# Power.net
KiCad netlist of a schematic drawn in Altium Designer
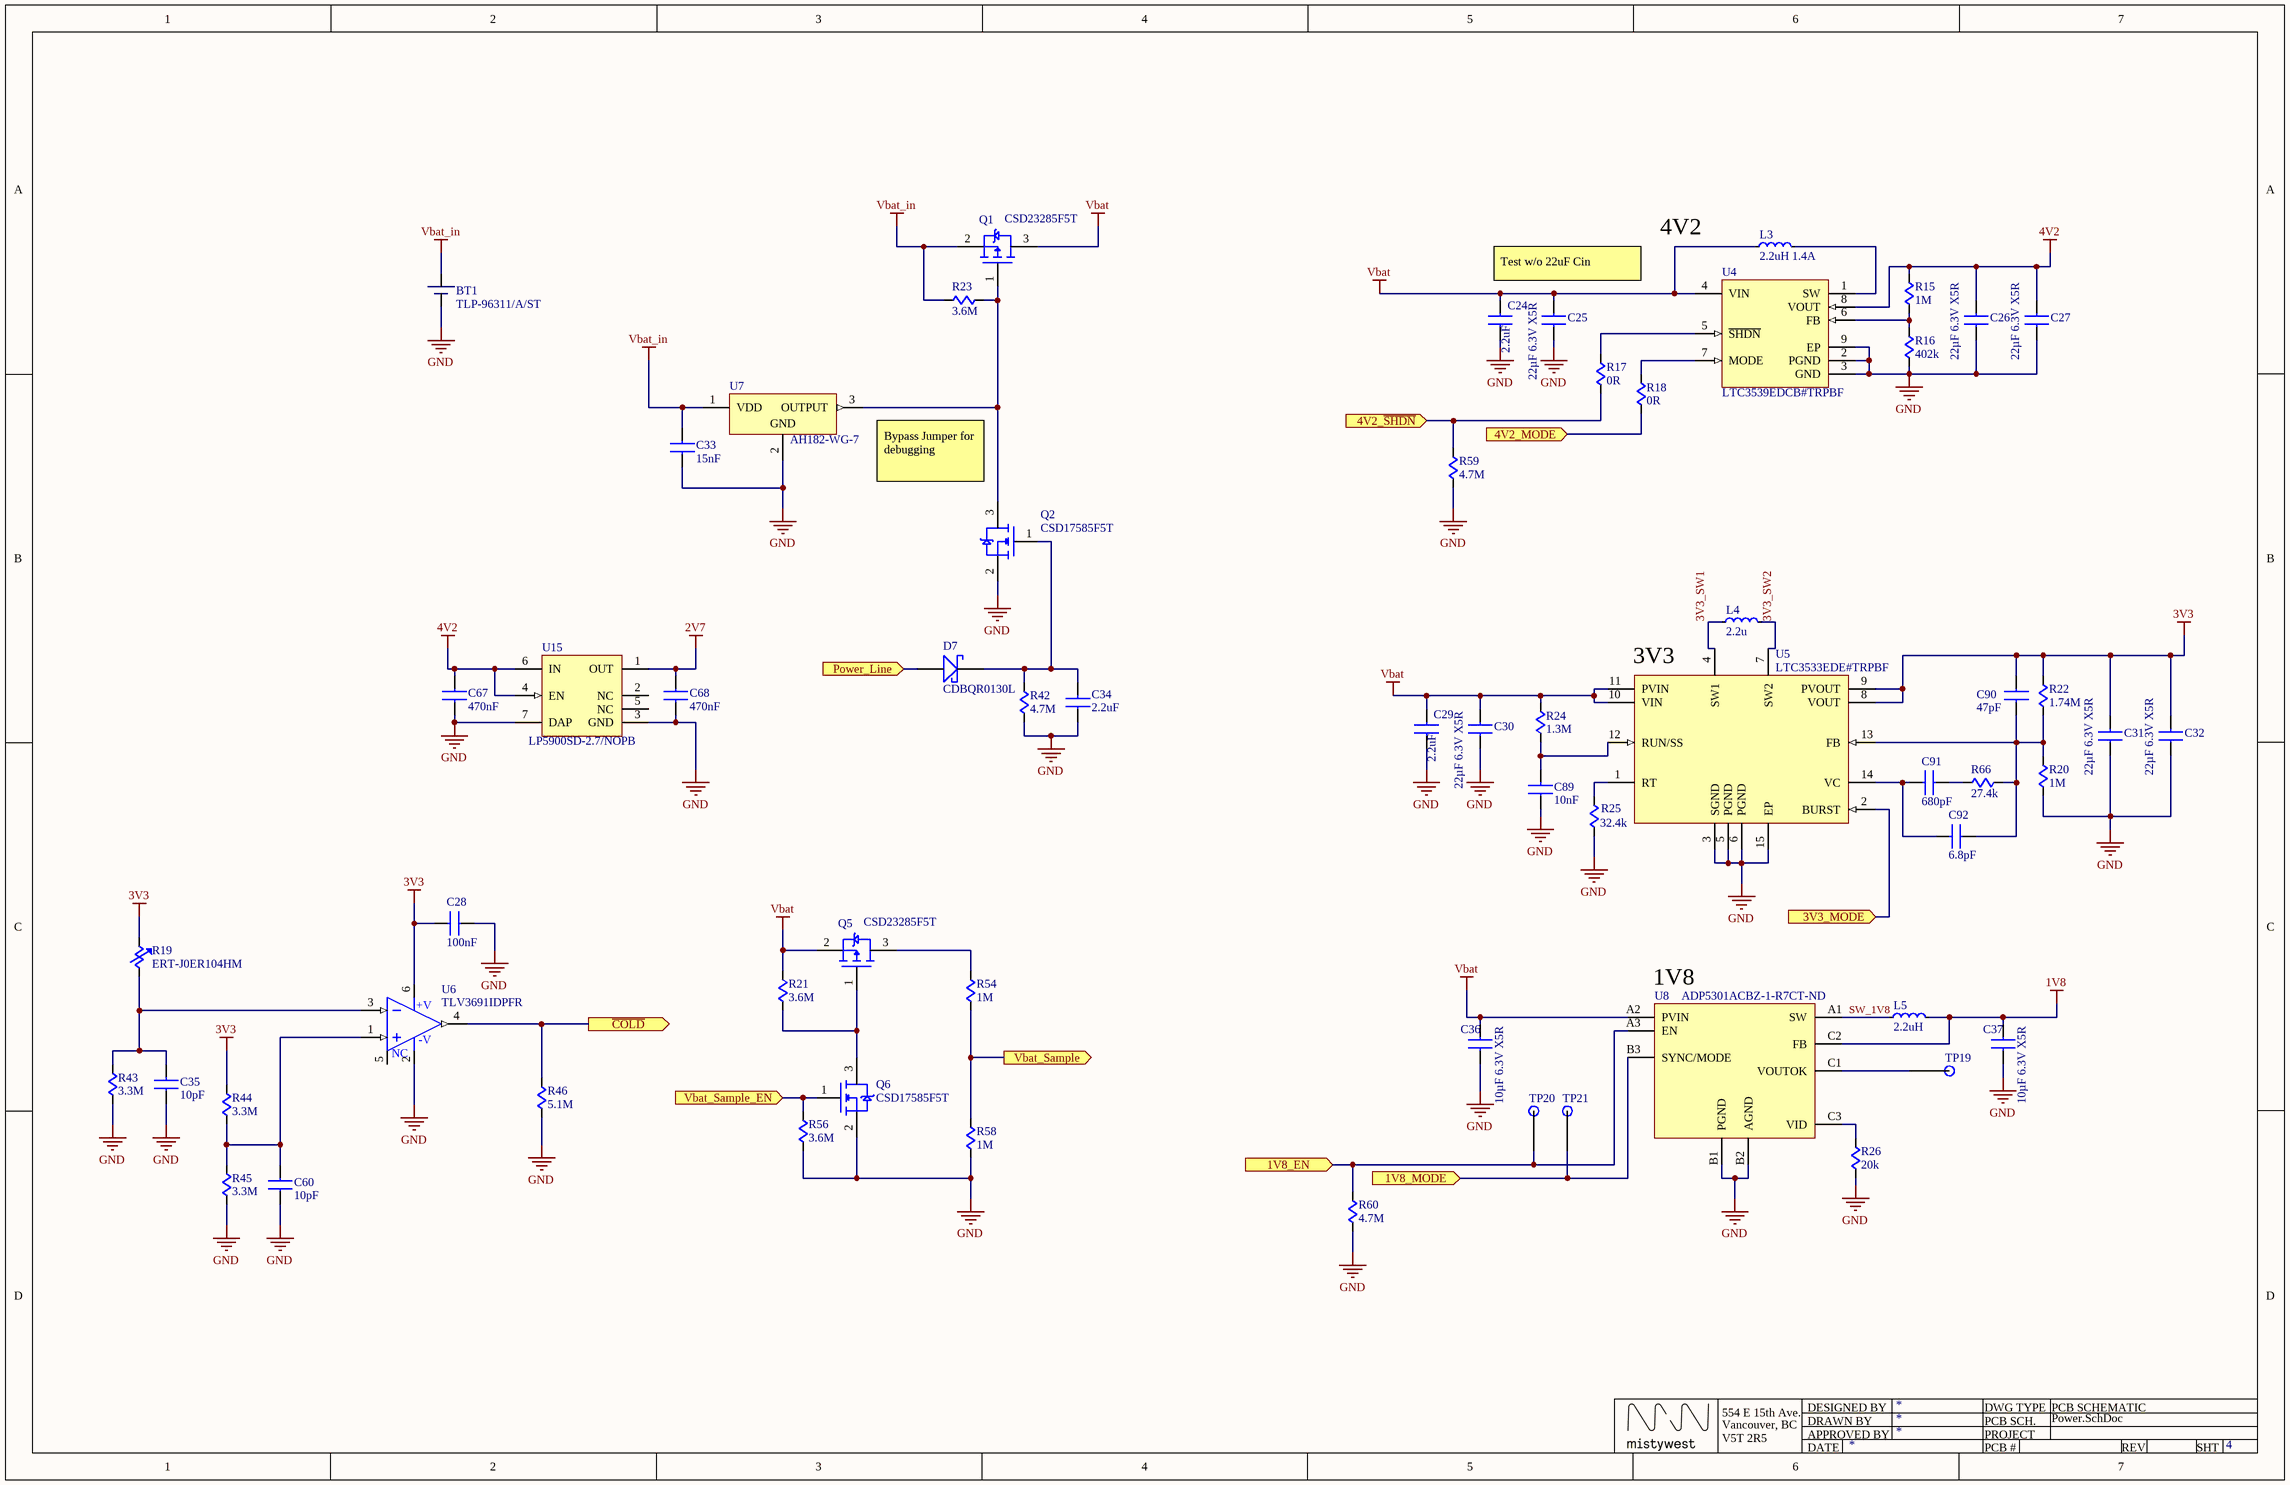
[diagram p0: Power.SchDoc]

(export (version "E")
  (design (tool "Eeschema 10.0.6"))
  (components
    (comp (ref "BT1")
      (value "TLP-96311/A/ST")
      (footprint "TLP-96311/A/ST")
      (fields (field (name "MANUFACTURER") "Tadiran"))
      (libsource (lib "Misty West") (part "1C"))
    )
    (comp (ref "C24")
      (value "2.2uF")
      (footprint "CAPC1608N-0603")
      (description "CAP CER 2.2uF 6.3V X7R 0603 ±10%")
      (fields
        (field (name "MANUFACTURER") "Samsung Electro-Mechanics America, Inc.")
        (field (name "MANUFACTURER PART NUMBER") "CL10B225KQ8NNNC")
      )
      (libsource (lib "") (part "Component_1_1"))
    )
    (comp (ref "C25")
      (value "22µF 6.3V X5R")
      (footprint "CAPC1608N-0603")
      (description "CAP CER 22UF 6.3V X5R 0603 ±10%")
      (fields
        (field (name "MANUFACTURER") "Samsung Electro-Mechanics America, Inc.")
        (field (name "MANUFACTURER PART NUMBER") "CL10A226KQ8NRNE")
      )
      (libsource (lib "") (part "Component_1_1"))
    )
    (comp (ref "C26")
      (value "22µF 6.3V X5R")
      (footprint "CAPC1608N-0603")
      (description "CAP CER 22UF 6.3V X5R 0603 ±10%")
      (fields
        (field (name "MANUFACTURER") "Samsung Electro-Mechanics America, Inc.")
        (field (name "MANUFACTURER PART NUMBER") "CL10A226KQ8NRNE")
      )
      (libsource (lib "") (part "Component_1_1"))
    )
    (comp (ref "C27")
      (value "22µF 6.3V X5R")
      (footprint "CAPC1608N-0603")
      (description "CAP CER 22UF 6.3V X5R 0603 ±10%")
      (fields
        (field (name "MANUFACTURER") "Samsung Electro-Mechanics America, Inc.")
        (field (name "MANUFACTURER PART NUMBER") "CL10A226KQ8NRNE")
      )
      (libsource (lib "") (part "Component_1_1"))
    )
    (comp (ref "C28")
      (value "100nF")
      (footprint "CAPC1005N-0402")
      (description "CAP CER 0.1UF 10V X7R 0402 ±5%")
      (fields
        (field (name "MANUFACTURER") "Samsung Electro-Mechanics America, Inc.")
        (field (name "MANUFACTURER PART NUMBER") "CL05B104JP5NNNC")
      )
      (libsource (lib "") (part "Component_1_1"))
    )
    (comp (ref "C29")
      (value "2.2uF")
      (footprint "CAPC1608N-0603")
      (description "CAP CER 2.2uF 6.3V X7R 0603 ±10%")
      (fields
        (field (name "MANUFACTURER") "Samsung Electro-Mechanics America, Inc.")
        (field (name "MANUFACTURER PART NUMBER") "CL10B225KQ8NNNC")
      )
      (libsource (lib "") (part "Component_1_1"))
    )
    (comp (ref "C30")
      (value "22µF 6.3V X5R")
      (footprint "CAPC1608N-0603")
      (description "CAP CER 22UF 6.3V X5R 0603 ±10%")
      (fields
        (field (name "MANUFACTURER") "Samsung Electro-Mechanics America, Inc.")
        (field (name "MANUFACTURER PART NUMBER") "CL10A226KQ8NRNE")
      )
      (libsource (lib "") (part "Component_1_1"))
    )
    (comp (ref "C31")
      (value "22µF 6.3V X5R")
      (footprint "CAPC1608N-0603")
      (description "CAP CER 22UF 6.3V X5R 0603 ±10%")
      (fields
        (field (name "MANUFACTURER") "Samsung Electro-Mechanics America, Inc.")
        (field (name "MANUFACTURER PART NUMBER") "CL10A226KQ8NRNE")
      )
      (libsource (lib "") (part "Component_1_1"))
    )
    (comp (ref "C32")
      (value "22µF 6.3V X5R")
      (footprint "CAPC1608N-0603")
      (description "CAP CER 22UF 6.3V X5R 0603 ±10%")
      (fields
        (field (name "MANUFACTURER") "Samsung Electro-Mechanics America, Inc.")
        (field (name "MANUFACTURER PART NUMBER") "CL10A226KQ8NRNE")
      )
      (libsource (lib "") (part "Component_1_1"))
    )
    (comp (ref "C33")
      (value "15nF")
      (footprint "CAPC60X30X33L15N")
      (description "CAP CER 15nF 6.3V X5R 0201 ±10%")
      (fields
        (field (name "MANUFACTURER") "Samsung Electro-Mechanics America, Inc.")
        (field (name "MANUFACTURER PART NUMBER") "CL03A153KQ3NNNC")
      )
      (libsource (lib "") (part "Component_1_1"))
    )
    (comp (ref "C34")
      (value "2.2uF")
      (footprint "CAPC1608N-0603")
      (description "CAP CER 2.2uF 6.3V X7R 0603 ±10%")
      (fields
        (field (name "MANUFACTURER") "Samsung Electro-Mechanics America, Inc.")
        (field (name "MANUFACTURER PART NUMBER") "CL10B225KQ8NNNC")
      )
      (libsource (lib "") (part "Component_1_1"))
    )
    (comp (ref "C35")
      (value "10pF")
      (footprint "CAPC1005N-0402")
      (description "CAP CER 10PF 50V C0G/NP0 0402 ±0.5pF")
      (fields
        (field (name "MANUFACTURER") "Samsung Electro-Mechanics America, Inc.")
        (field (name "MANUFACTURER PART NUMBER") "CL05C100DB5NNNC")
      )
      (libsource (lib "") (part "Component_1_1"))
    )
    (comp (ref "C36")
      (value "10µF 6.3V X5R")
      (footprint "CAPC1608N-0603")
      (description "CAP CER 10UF 6.3V X5R 0603 ±10%")
      (fields
        (field (name "MANUFACTURER") "Samsung Electro-Mechanics America, Inc.")
        (field (name "MANUFACTURER PART NUMBER") "CL10A106KQ8NNNC")
      )
      (libsource (lib "") (part "Component_1_1"))
    )
    (comp (ref "C37")
      (value "10µF 6.3V X5R")
      (footprint "CAPC1608N-0603")
      (description "CAP CER 10UF 6.3V X5R 0603 ±10%")
      (fields
        (field (name "MANUFACTURER") "Samsung Electro-Mechanics America, Inc.")
        (field (name "MANUFACTURER PART NUMBER") "CL10A106KQ8NNNC")
      )
      (libsource (lib "") (part "Component_1_1"))
    )
    (comp (ref "C60")
      (value "10pF")
      (footprint "CAPC1005N-0402")
      (description "CAP CER 10PF 50V C0G/NP0 0402 ±0.5pF")
      (fields
        (field (name "MANUFACTURER") "Samsung Electro-Mechanics America, Inc.")
        (field (name "MANUFACTURER PART NUMBER") "CL05C100DB5NNNC")
      )
      (libsource (lib "") (part "Component_1_1"))
    )
    (comp (ref "C67")
      (value "470nF")
      (footprint "CAPC60X30X33L15N")
      (description "CAP CER 470nF 6.3V X5R 0201 ±10%")
      (fields
        (field (name "MANUFACTURER") "Samsung Electro-Mechanics America, Inc.")
        (field (name "MANUFACTURER PART NUMBER") "CL03A474KQ3NNNC")
      )
      (libsource (lib "") (part "Component_1_1"))
    )
    (comp (ref "C68")
      (value "470nF")
      (footprint "CAPC60X30X33L15N")
      (description "CAP CER 470nF 6.3V X5R 0201 ±10%")
      (fields
        (field (name "MANUFACTURER") "Samsung Electro-Mechanics America, Inc.")
        (field (name "MANUFACTURER PART NUMBER") "CL03A474KQ3NNNC")
      )
      (libsource (lib "") (part "Component_1_1"))
    )
    (comp (ref "C89")
      (value "10nF")
      (footprint "CAPC1005N-0402")
      (description "CAP CER 10000PF 10V X7R 0402 ±10%")
      (fields
        (field (name "MANUFACTURER") "Samsung Electro-Mechanics America, Inc.")
        (field (name "MANUFACTURER PART NUMBER") "CL05B103KP5NNNC")
      )
      (libsource (lib "") (part "Component_1_1"))
    )
    (comp (ref "C90")
      (value "47pF")
      (footprint "CAPC1005N-0402")
      (description "CAP CER 47PF 50V C0G/NP0 0402 ±5% AEC-Q200")
      (fields
        (field (name "MANUFACTURER") "Samsung Electro-Mechanics America, Inc.")
        (field (name "MANUFACTURER PART NUMBER") "CL05C470JB51PNC")
      )
      (libsource (lib "") (part "Component_1_1"))
    )
    (comp (ref "C91")
      (value "680pF")
      (footprint "CAPC1005N-0402")
      (description "CAP CER 680PF 50V C0G/NP0 0402 ±5%")
      (fields
        (field (name "MANUFACTURER") "Samsung Electro-Mechanics America, Inc.")
        (field (name "MANUFACTURER PART NUMBER") "CL05C681JB5NNNC")
      )
      (libsource (lib "") (part "Component_1_1"))
    )
    (comp (ref "C92")
      (value "6.8pF")
      (footprint "CAPC1005N-0402")
      (description "CAP CER 6.8PF 50V C0G/NP0 0402 ±0.25pF")
      (fields
        (field (name "MANUFACTURER") "Samsung Electro-Mechanics America, Inc.")
        (field (name "MANUFACTURER PART NUMBER") "CL05C6R8CB5NNNC")
      )
      (libsource (lib "") (part "Component_1_1"))
    )
    (comp (ref "D7")
      (value "CDBQR0130L")
      (footprint "CDBQR0130L")
      (description "Diode Schottky 30V 100mA Surface Mount 0402/SOD-923F")
      (fields (field (name "MANUFACTURER") "Comchip Technology"))
      (libsource (lib "") (part "Component_1_2"))
    )
    (comp (ref "L3")
      (value "2.2uH 1.4A")
      (footprint "XFL3012")
      (description "XFL3012-222ME_")
      (fields (field (name "MANUFACTURER") "CoilCraft"))
      (libsource (lib "") (part "Component_1_4"))
    )
    (comp (ref "L4")
      (value "2.2u")
      (footprint "XAL4020")
      (description "XAL4020-222ME")
      (fields (field (name "MANUFACTURER") "CoilCraft"))
      (libsource (lib "") (part "Component_1_4"))
    )
    (comp (ref "L5")
      (value "2.2uH")
      (footprint "XPL2010")
      (description "XPL2010-222ML")
      (fields (field (name "MANUFACTURER") "CoilCraft"))
      (libsource (lib "") (part "Component_1_4"))
    )
    (comp (ref "Q1")
      (value "CSD23285F5T")
      (footprint "3-XFDFN")
      (description "P-Channel 12V 5.4A (Ta) 500mW (Ta) Surface Mount 3-PICOSTAR")
      (fields (field (name "MANUFACTURER") "Texas Instruments"))
      (libsource (lib "Misty West") (part "Mosfet-P-CH, 8Pin"))
    )
    (comp (ref "Q2")
      (value "CSD17585F5T")
      (footprint "3-XFDFN")
      (description "N-Channel 30V 5.9A (Ta) 500mW (Ta) Surface Mount 3-PICOSTAR")
      (fields (field (name "MANUFACTURER") "Texas Instruments"))
      (libsource (lib "") (part "Component_1_3"))
    )
    (comp (ref "Q5")
      (value "CSD23285F5T")
      (footprint "3-XFDFN")
      (description "P-Channel 12V 5.4A (Ta) 500mW (Ta) Surface Mount 3-PICOSTAR")
      (fields (field (name "MANUFACTURER") "Texas Instruments"))
      (libsource (lib "Misty West") (part "Mosfet-P-CH, 8Pin"))
    )
    (comp (ref "Q6")
      (value "CSD17585F5T")
      (footprint "3-XFDFN")
      (description "N-Channel 30V 5.9A (Ta) 500mW (Ta) Surface Mount 3-PICOSTAR")
      (fields (field (name "MANUFACTURER") "Texas Instruments"))
      (libsource (lib "") (part "Component_1_3"))
    )
    (comp (ref "R15")
      (value "1M")
      (footprint "RESC0402(1005)_N")
      (description "RES SMD 1M OHM 1% 1/16W 0402")
      (fields
        (field (name "MANUFACTURER") "Yageo")
        (field (name "MANUFACTURER PART NUMBER") "RC0402FR-071ML")
      )
      (libsource (lib "Misty West") (part "Component_1"))
    )
    (comp (ref "R16")
      (value "402k")
      (footprint "RESC0402(1005)_N")
      (description "RES SMD 402K OHM 1% 1/10W 0402")
      (fields
        (field (name "MANUFACTURER") "Panasonic Electronic Components")
        (field (name "MANUFACTURER PART NUMBER") "ERJ-2RKF4023X")
      )
      (libsource (lib "Misty West") (part "Component_1"))
    )
    (comp (ref "R17")
      (value "0R")
      (footprint "Chip Res 1608_0603 MMC")
      (description "0R 0.1W")
      (fields
        (field (name "MANUFACTURER") "Yageo")
        (field (name "MANUFACTURER PART NUMBER") "RC0603JR-070RL")
      )
      (libsource (lib "Misty West") (part "Component_1"))
    )
    (comp (ref "R18")
      (value "0R")
      (footprint "Chip Res 1608_0603 MMC")
      (description "0R 0.1W")
      (fields
        (field (name "MANUFACTURER") "Yageo")
        (field (name "MANUFACTURER PART NUMBER") "RC0603JR-070RL")
      )
      (libsource (lib "Misty West") (part "Component_1"))
    )
    (comp (ref "R19")
      (value "ERT-J0ER104HM")
      (footprint "RESC0402(1005)_N")
      (description "NTC Thermistor 100k 0402 (1005 Metric)")
      (fields (field (name "MANUFACTURER") "Panasonic Electronic Components") (field (name "POWER") "66mW"))
      (libsource (lib "") (part "Component_1_5"))
    )
    (comp (ref "R20")
      (value "1M")
      (footprint "RESC0402(1005)_N")
      (description "RES SMD 1M OHM 1% 1/16W 0402")
      (fields
        (field (name "MANUFACTURER") "Yageo")
        (field (name "MANUFACTURER PART NUMBER") "RC0402FR-071ML")
      )
      (libsource (lib "Misty West") (part "Component_1"))
    )
    (comp (ref "R21")
      (value "3.6M")
      (footprint "RESC0402(1005)_N")
      (description "RES SMD 3.6M OHM 1% 1/16W 0402")
      (fields
        (field (name "MANUFACTURER") "Yageo")
        (field (name "MANUFACTURER PART NUMBER") "RC0402FR-073M6L")
      )
      (libsource (lib "Misty West") (part "Component_1"))
    )
    (comp (ref "R22")
      (value "1.74M")
      (footprint "RESC0402(1005)_N")
      (description "RES SMD 1.74M OHM 1% 1/16W 0402")
      (fields
        (field (name "MANUFACTURER") "Yageo")
        (field (name "MANUFACTURER PART NUMBER") "RC0402FR-071M74L")
      )
      (libsource (lib "Misty West") (part "Component_1"))
    )
    (comp (ref "R23")
      (value "3.6M")
      (footprint "RESC0402(1005)_N")
      (description "RES SMD 3.6M OHM 1% 1/16W 0402")
      (fields
        (field (name "MANUFACTURER") "Yageo")
        (field (name "MANUFACTURER PART NUMBER") "RC0402FR-073M6L")
      )
      (libsource (lib "Misty West") (part "Component_1"))
    )
    (comp (ref "R24")
      (value "1.3M")
      (footprint "RESC0402(1005)_N")
      (description "RES SMD 1.3M OHM 1% 1/16W 0402")
      (fields
        (field (name "MANUFACTURER") "Yageo")
        (field (name "MANUFACTURER PART NUMBER") "RC0402FR-071M3L")
      )
      (libsource (lib "Misty West") (part "Component_1"))
    )
    (comp (ref "R25")
      (value "32.4k")
      (footprint "RESC0402(1005)_N")
      (description "RES SMD 32.4K OHM 1% 1/10W 0402")
      (fields
        (field (name "MANUFACTURER") "Panasonic Electronic Components")
        (field (name "MANUFACTURER PART NUMBER") "ERJ-2RKF3242X")
      )
      (libsource (lib "Misty West") (part "Component_1"))
    )
    (comp (ref "R26")
      (value "20k")
      (footprint "RESC0402(1005)_N")
      (description "RES SMD 20K OHM 1% 1/10W 0402")
      (fields
        (field (name "MANUFACTURER") "Panasonic Electronic Components")
        (field (name "MANUFACTURER PART NUMBER") "ERJ-2RKF2002X")
      )
      (libsource (lib "Misty West") (part "Component_1"))
    )
    (comp (ref "R42")
      (value "4.7M")
      (footprint "Chip Res 1608_0603 MMC")
      (description "RES SMD 4.7M ±1% 0.1W, 1/10W 0603")
      (fields
        (field (name "MANUFACTURER") "Yageo")
        (field (name "MANUFACTURER PART NUMBER") "RC0603FR-074M7L")
      )
      (libsource (lib "Misty West") (part "Component_1"))
    )
    (comp (ref "R43")
      (value "3.3M")
      (footprint "RESC0402(1005)_N")
      (description "RES SMD 3.3M OHM 1% 1/16W 0402")
      (fields
        (field (name "MANUFACTURER") "Yageo")
        (field (name "MANUFACTURER PART NUMBER") "RC0402FR-073M3L")
      )
      (libsource (lib "Misty West") (part "Component_1"))
    )
    (comp (ref "R44")
      (value "3.3M")
      (footprint "RESC0402(1005)_N")
      (description "RES SMD 3.3M OHM 1% 1/16W 0402")
      (fields
        (field (name "MANUFACTURER") "Yageo")
        (field (name "MANUFACTURER PART NUMBER") "RC0402FR-073M3L")
      )
      (libsource (lib "Misty West") (part "Component_1"))
    )
    (comp (ref "R45")
      (value "3.3M")
      (footprint "RESC0402(1005)_N")
      (description "RES SMD 3.3M OHM 1% 1/16W 0402")
      (fields
        (field (name "MANUFACTURER") "Yageo")
        (field (name "MANUFACTURER PART NUMBER") "RC0402FR-073M3L")
      )
      (libsource (lib "Misty West") (part "Component_1"))
    )
    (comp (ref "R46")
      (value "5.1M")
      (footprint "RESC0402(1005)_N")
      (description "RES SMD 5.1M OHM 1% 1/16W 0402")
      (fields
        (field (name "MANUFACTURER") "Yageo")
        (field (name "MANUFACTURER PART NUMBER") "RC0402FR-075M1L")
      )
      (libsource (lib "Misty West") (part "Component_1"))
    )
    (comp (ref "R54")
      (value "1M")
      (footprint "RESC0402(1005)_N")
      (description "RES SMD 1M OHM 1% 1/10W 0402")
      (fields
        (field (name "MANUFACTURER") "Panasonic Electronic Components")
        (field (name "MANUFACTURER PART NUMBER") "ERJ-2RKF1004X")
      )
      (libsource (lib "Misty West") (part "Component_1"))
    )
    (comp (ref "R56")
      (value "3.6M")
      (footprint "RESC0402(1005)_N")
      (description "RES SMD 3.6M OHM 1% 1/16W 0402")
      (fields
        (field (name "MANUFACTURER") "Yageo")
        (field (name "MANUFACTURER PART NUMBER") "RC0402FR-073M6L")
      )
      (libsource (lib "Misty West") (part "Component_1"))
    )
    (comp (ref "R58")
      (value "1M")
      (footprint "RESC0402(1005)_N")
      (description "RES SMD 1M OHM 1% 1/10W 0402")
      (fields
        (field (name "MANUFACTURER") "Panasonic Electronic Components")
        (field (name "MANUFACTURER PART NUMBER") "ERJ-2RKF1004X")
      )
      (libsource (lib "Misty West") (part "Component_1"))
    )
    (comp (ref "R59")
      (value "4.7M")
      (footprint "Chip Res 1608_0603 MMC")
      (description "RES SMD 4.7M ±1% 0.1W, 1/10W 0603")
      (fields
        (field (name "MANUFACTURER") "Yageo")
        (field (name "MANUFACTURER PART NUMBER") "RC0603FR-074M7L")
      )
      (libsource (lib "Misty West") (part "Component_1"))
    )
    (comp (ref "R60")
      (value "4.7M")
      (footprint "Chip Res 1608_0603 MMC")
      (description "RES SMD 4.7M ±1% 0.1W, 1/10W 0603")
      (fields
        (field (name "MANUFACTURER") "Yageo")
        (field (name "MANUFACTURER PART NUMBER") "RC0603FR-074M7L")
      )
      (libsource (lib "Misty West") (part "Component_1"))
    )
    (comp (ref "R66")
      (value "27.4k")
      (footprint "RESC0402(1005)_N")
      (description "RES SMD 27.4KOHM 0.1% 1/16W 0402 ±10ppm/°C")
      (fields
        (field (name "MANUFACTURER") "TE Connectivity Passive Product")
        (field (name "MANUFACTURER PART NUMBER") "RN73C1E27K4BTD")
      )
      (libsource (lib "Misty West") (part "Component_1"))
    )
    (comp (ref "TP19")
      (value "~")
      (footprint "Testpoint_16mil_32mil")
      (description "Test Point - 16mil/32mil via")
      (libsource (lib "Misty West") (part "TestPoint_NoPart"))
    )
    (comp (ref "TP20")
      (value "~")
      (footprint "Testpoint_16mil_32mil")
      (description "Test Point - 16mil/32mil via")
      (libsource (lib "Misty West") (part "TestPoint_NoPart"))
    )
    (comp (ref "TP21")
      (value "~")
      (footprint "Testpoint_16mil_32mil")
      (description "Test Point - 16mil/32mil via")
      (libsource (lib "Misty West") (part "TestPoint_NoPart"))
    )
    (comp (ref "U4")
      (value "LTC3539EDCB#TRPBF")
      (footprint "LT-DCB-8_V")
      (fields (field (name "MANUFACTURER") "Linear Technology"))
      (libsource (lib "Misty West") (part "LT-LTC3539-DCB-8"))
    )
    (comp (ref "U5")
      (value "LTC3533EDE#TRPBF")
      (footprint "LT-DE-14_V")
      (fields (field (name "MANUFACTURER") "Linear Technology"))
      (libsource (lib "Misty West") (part "LT-LTC3533-DE-14"))
    )
    (comp (ref "U6")
      (value "TLV3691IDPFR")
      (footprint "6-X2SON (1x1)")
      (description "Comparator General Purpose Push-Pull 6-X2SON (1x1)")
      (fields (field (name "MANUFACTURER") "Texas Instruments"))
      (libsource (lib "Misty West") (part "OP_AMP"))
    )
    (comp (ref "U7")
      (value "AH182-WG-7")
      (footprint "DIOD-SC59-3_L")
      (description "Low Power Hall Effect Switch, 2.5 to 5.5 V, -40 to 85 degC, 3-Pin SC59, RoHS, Tape and Reel")
      (fields (field (name "MANUFACTURER") "Diodes Incorporated"))
      (libsource (lib "Misty West") (part "DIOD-AH182-SC59-3"))
    )
    (comp (ref "U8")
      (value "ADP5301ACBZ-1-R7CT-ND")
      (footprint "9-Ball WLCSP")
      (description "Buck Switching Regulator IC Positive Programmable 0.8V 1 Output 50mA, 500mA 9-WFBGA, WLCSP")
      (fields (field (name "MANUFACTURER") "ADP5301ACBZ-1-R7"))
      (libsource (lib "Misty West") (part "ADP5301"))
    )
    (comp (ref "U15")
      (value "LP5900SD-2.7/NOPB")
      (footprint "NGF0006A_V")
      (fields (field (name "MANUFACTURER") "Texas Instruments"))
      (libsource (lib "Misty West") (part "PM-REG-LP5900-IL7"))
    )
  )
  (nets
    (net (code "1") (name "/1V8_EN") (class "Default")
      (node (ref "R60") (pin "2") (pintype "passive"))
      (node (ref "TP20") (pin "TP") (pinfunction "TP_TP") (pintype "passive"))
      (node (ref "U8") (pin "A3") (pinfunction "EN_A3") (pintype "passive"))
    )
    (net (code "2") (name "/1V8_MODE") (class "Default")
      (node (ref "TP21") (pin "TP") (pinfunction "TP_TP") (pintype "passive"))
      (node (ref "U8") (pin "B3") (pinfunction "SYNC/MODE_B3") (pintype "passive"))
    )
    (net (code "3") (name "/3V3_MODE") (class "Default")
      (node (ref "U5") (pin "2") (pinfunction "BURST_2") (pintype "input"))
    )
    (net (code "4") (name "/3V3_SW1") (class "Default")
      (node (ref "L4") (pin "1") (pinfunction "1_1") (pintype "passive"))
      (node (ref "U5") (pin "4") (pinfunction "SW1_4") (pintype "passive"))
    )
    (net (code "5") (name "/3V3_SW2") (class "Default")
      (node (ref "L4") (pin "2") (pinfunction "2_2") (pintype "passive"))
      (node (ref "U5") (pin "7") (pinfunction "SW2_7") (pintype "passive"))
    )
    (net (code "6") (name "/4V2_MODE") (class "Default") (node (ref "R18") (pin "1") (pintype "passive")))
    (net (code "7") (name "/4V2_~{SHDN}") (class "Default")
      (node (ref "R17") (pin "1") (pintype "passive"))
      (node (ref "R59") (pin "2") (pintype "passive"))
    )
    (net (code "8") (name "/Power_Line") (class "Default")
      (node (ref "D7") (pin "1") (pinfunction "Anode_1") (pintype "passive"))
    )
    (net (code "9") (name "/SW_1V8") (class "Default")
      (node (ref "L5") (pin "1") (pinfunction "1_1") (pintype "passive"))
      (node (ref "U8") (pin "A1") (pinfunction "SW_A1") (pintype "passive"))
    )
    (net (code "10") (name "/Vbat_Sample") (class "Default")
      (node (ref "R54") (pin "1") (pintype "passive"))
      (node (ref "R58") (pin "2") (pintype "passive"))
    )
    (net (code "11") (name "/Vbat_Sample_EN") (class "Default")
      (node (ref "Q6") (pin "1") (pinfunction "Gate_1") (pintype "passive"))
      (node (ref "R56") (pin "1") (pintype "passive"))
    )
    (net (code "12") (name "/~{COLD}") (class "Default")
      (node (ref "R46") (pin "2") (pintype "passive"))
      (node (ref "U6") (pin "4") (pinfunction "OUT_A_4") (pintype "output"))
    )
    (net (code "13") (name "1V8") (class "Default")
      (node (ref "C37") (pin "1") (pintype "passive"))
      (node (ref "L5") (pin "2") (pinfunction "2_2") (pintype "passive"))
      (node (ref "U8") (pin "C2") (pinfunction "FB_C2") (pintype "passive"))
    )
    (net (code "14") (name "2V7") (class "Default")
      (node (ref "C68") (pin "1") (pintype "passive"))
      (node (ref "U15") (pin "1") (pinfunction "OUT_1") (pintype "power_in"))
    )
    (net (code "15") (name "3V3") (class "Default")
      (node (ref "C28") (pin "1") (pintype "passive"))
      (node (ref "C31") (pin "1") (pintype "passive"))
      (node (ref "C32") (pin "1") (pintype "passive"))
      (node (ref "C90") (pin "1") (pintype "passive"))
      (node (ref "R19") (pin "1") (pintype "passive"))
      (node (ref "R22") (pin "2") (pintype "passive"))
      (node (ref "R44") (pin "2") (pintype "passive"))
      (node (ref "U5") (pin "8") (pinfunction "VOUT_8") (pintype "power_in"))
      (node (ref "U5") (pin "9") (pinfunction "PVOUT_9") (pintype "power_in"))
      (node (ref "U6") (pin "6") (pinfunction "V+_6") (pintype "power_in"))
    )
    (net (code "16") (name "4V2") (class "Default")
      (node (ref "C26") (pin "1") (pintype "passive"))
      (node (ref "C27") (pin "1") (pintype "passive"))
      (node (ref "C67") (pin "1") (pintype "passive"))
      (node (ref "R15") (pin "2") (pintype "passive"))
      (node (ref "U15") (pin "4") (pinfunction "EN_4") (pintype "input"))
      (node (ref "U15") (pin "6") (pinfunction "IN_6") (pintype "power_in"))
      (node (ref "U4") (pin "8") (pinfunction "VOUT_8") (pintype "input"))
    )
    (net (code "17") (name "GND") (class "Default")
      (node (ref "BT1") (pin "2") (pinfunction "2_2") (pintype "passive"))
      (node (ref "C24") (pin "2") (pintype "passive"))
      (node (ref "C25") (pin "2") (pintype "passive"))
      (node (ref "C26") (pin "2") (pintype "passive"))
      (node (ref "C27") (pin "2") (pintype "passive"))
      (node (ref "C28") (pin "2") (pintype "passive"))
      (node (ref "C29") (pin "2") (pintype "passive"))
      (node (ref "C30") (pin "2") (pintype "passive"))
      (node (ref "C31") (pin "2") (pintype "passive"))
      (node (ref "C32") (pin "2") (pintype "passive"))
      (node (ref "C33") (pin "2") (pintype "passive"))
      (node (ref "C34") (pin "2") (pintype "passive"))
      (node (ref "C35") (pin "2") (pintype "passive"))
      (node (ref "C36") (pin "2") (pintype "passive"))
      (node (ref "C37") (pin "2") (pintype "passive"))
      (node (ref "C60") (pin "2") (pintype "passive"))
      (node (ref "C67") (pin "2") (pintype "passive"))
      (node (ref "C68") (pin "2") (pintype "passive"))
      (node (ref "C89") (pin "2") (pintype "passive"))
      (node (ref "Q2") (pin "2") (pinfunction "Source_2") (pintype "passive"))
      (node (ref "Q6") (pin "2") (pinfunction "Source_2") (pintype "passive"))
      (node (ref "R16") (pin "1") (pintype "passive"))
      (node (ref "R20") (pin "1") (pintype "passive"))
      (node (ref "R25") (pin "1") (pintype "passive"))
      (node (ref "R26") (pin "1") (pintype "passive"))
      (node (ref "R42") (pin "1") (pintype "passive"))
      (node (ref "R43") (pin "1") (pintype "passive"))
      (node (ref "R45") (pin "1") (pintype "passive"))
      (node (ref "R46") (pin "1") (pintype "passive"))
      (node (ref "R56") (pin "2") (pintype "passive"))
      (node (ref "R58") (pin "1") (pintype "passive"))
      (node (ref "R59") (pin "1") (pintype "passive"))
      (node (ref "R60") (pin "1") (pintype "passive"))
      (node (ref "U15") (pin "3") (pinfunction "GND_3") (pintype "power_in"))
      (node (ref "U15") (pin "7") (pinfunction "DAP_7") (pintype "power_in"))
      (node (ref "U4") (pin "2") (pinfunction "PGND_2") (pintype "power_in"))
      (node (ref "U4") (pin "3") (pinfunction "GND_3") (pintype "power_in"))
      (node (ref "U4") (pin "9") (pinfunction "EP_9") (pintype "power_in"))
      (node (ref "U5") (pin "15") (pinfunction "EP_15") (pintype "power_in"))
      (node (ref "U5") (pin "3") (pinfunction "SGND_3") (pintype "power_in"))
      (node (ref "U5") (pin "5") (pinfunction "PGND_5") (pintype "power_in"))
      (node (ref "U5") (pin "6") (pinfunction "PGND_6") (pintype "power_in"))
      (node (ref "U6") (pin "2") (pinfunction "V-_2") (pintype "power_in"))
      (node (ref "U7") (pin "2") (pinfunction "GND_2") (pintype "power_in"))
      (node (ref "U8") (pin "B1") (pinfunction "PGND_B1") (pintype "passive"))
      (node (ref "U8") (pin "B2") (pinfunction "AGND_B2") (pintype "passive"))
    )
    (net (code "18") (name "Net-(C91-Pad2)") (class "Default")
      (node (ref "C91") (pin "2") (pintype "passive"))
      (node (ref "R66") (pin "2") (pintype "passive"))
    )
    (net (code "19") (name "Net-(D7-Cathode)") (class "Default")
      (node (ref "C34") (pin "1") (pintype "passive"))
      (node (ref "D7") (pin "2") (pinfunction "Cathode_2") (pintype "passive"))
      (node (ref "Q2") (pin "1") (pinfunction "Gate_1") (pintype "passive"))
      (node (ref "R42") (pin "2") (pintype "passive"))
    )
    (net (code "20") (name "Net-(Q1-Gate)") (class "Default")
      (node (ref "Q1") (pin "1") (pinfunction "Gate_1") (pintype "passive"))
      (node (ref "Q2") (pin "3") (pinfunction "Drain_3") (pintype "passive"))
      (node (ref "R23") (pin "1") (pintype "passive"))
      (node (ref "U7") (pin "3") (pinfunction "OUTPUT_3") (pintype "output"))
    )
    (net (code "21") (name "Net-(Q5-Drain)") (class "Default")
      (node (ref "Q5") (pin "3") (pinfunction "Drain_3") (pintype "passive"))
      (node (ref "R54") (pin "2") (pintype "passive"))
    )
    (net (code "22") (name "Net-(Q5-Gate)") (class "Default")
      (node (ref "Q5") (pin "1") (pinfunction "Gate_1") (pintype "passive"))
      (node (ref "Q6") (pin "3") (pinfunction "Drain_3") (pintype "passive"))
      (node (ref "R21") (pin "2") (pintype "passive"))
    )
    (net (code "23") (name "Net-(U4-FB)") (class "Default")
      (node (ref "R15") (pin "1") (pintype "passive"))
      (node (ref "R16") (pin "2") (pintype "passive"))
      (node (ref "U4") (pin "6") (pinfunction "FB_6") (pintype "input"))
    )
    (net (code "24") (name "Net-(U4-MODE)") (class "Default")
      (node (ref "R18") (pin "2") (pintype "passive"))
      (node (ref "U4") (pin "7") (pinfunction "MODE_7") (pintype "input"))
    )
    (net (code "25") (name "Net-(U4-SW)") (class "Default")
      (node (ref "L3") (pin "2") (pinfunction "2_2") (pintype "passive"))
      (node (ref "U4") (pin "1") (pinfunction "SW_1") (pintype "passive"))
    )
    (net (code "26") (name "Net-(U4-~{SHDN})") (class "Default")
      (node (ref "R17") (pin "2") (pintype "passive"))
      (node (ref "U4") (pin "5") (pinfunction "~{SHDN}_5") (pintype "input"))
    )
    (net (code "27") (name "Net-(U5-FB)") (class "Default")
      (node (ref "C90") (pin "2") (pintype "passive"))
      (node (ref "C92") (pin "2") (pintype "passive"))
      (node (ref "R20") (pin "2") (pintype "passive"))
      (node (ref "R22") (pin "1") (pintype "passive"))
      (node (ref "R66") (pin "1") (pintype "passive"))
      (node (ref "U5") (pin "13") (pinfunction "FB_13") (pintype "input"))
    )
    (net (code "28") (name "Net-(U5-RT)") (class "Default")
      (node (ref "R25") (pin "2") (pintype "passive"))
      (node (ref "U5") (pin "1") (pinfunction "RT_1") (pintype "passive"))
    )
    (net (code "29") (name "Net-(U5-RUN{slash}SS)") (class "Default")
      (node (ref "C89") (pin "1") (pintype "passive"))
      (node (ref "R24") (pin "1") (pintype "passive"))
      (node (ref "U5") (pin "12") (pinfunction "RUN/SS_12") (pintype "input"))
    )
    (net (code "30") (name "Net-(U5-VC)") (class "Default")
      (node (ref "C91") (pin "1") (pintype "passive"))
      (node (ref "C92") (pin "1") (pintype "passive"))
      (node (ref "U5") (pin "14") (pinfunction "VC_14") (pintype "passive"))
    )
    (net (code "31") (name "Net-(U6-+IN_A)") (class "Default")
      (node (ref "C60") (pin "1") (pintype "passive"))
      (node (ref "R44") (pin "1") (pintype "passive"))
      (node (ref "R45") (pin "2") (pintype "passive"))
      (node (ref "U6") (pin "1") (pinfunction "+IN_A_1") (pintype "input"))
    )
    (net (code "32") (name "Net-(U6--IN_A)") (class "Default")
      (node (ref "C35") (pin "1") (pintype "passive"))
      (node (ref "R19") (pin "2") (pintype "passive"))
      (node (ref "R43") (pin "2") (pintype "passive"))
      (node (ref "U6") (pin "3") (pinfunction "-IN_A_3") (pintype "input"))
    )
    (net (code "33") (name "Net-(U8-VID)") (class "Default")
      (node (ref "R26") (pin "2") (pintype "passive"))
      (node (ref "U8") (pin "C3") (pinfunction "VID_C3") (pintype "passive"))
    )
    (net (code "34") (name "Net-(U8-VOUTOK)") (class "Default")
      (node (ref "TP19") (pin "TP") (pinfunction "TP_TP") (pintype "passive"))
      (node (ref "U8") (pin "C1") (pinfunction "VOUTOK_C1") (pintype "passive"))
    )
    (net (code "35") (name "Vbat") (class "Default")
      (node (ref "C24") (pin "1") (pintype "passive"))
      (node (ref "C25") (pin "1") (pintype "passive"))
      (node (ref "C29") (pin "1") (pintype "passive"))
      (node (ref "C30") (pin "1") (pintype "passive"))
      (node (ref "C36") (pin "1") (pintype "passive"))
      (node (ref "L3") (pin "1") (pinfunction "1_1") (pintype "passive"))
      (node (ref "Q1") (pin "3") (pinfunction "Drain_3") (pintype "passive"))
      (node (ref "Q5") (pin "2") (pinfunction "Source_2") (pintype "passive"))
      (node (ref "R21") (pin "1") (pintype "passive"))
      (node (ref "R24") (pin "2") (pintype "passive"))
      (node (ref "U4") (pin "4") (pinfunction "VIN_4") (pintype "power_in"))
      (node (ref "U5") (pin "10") (pinfunction "VIN_10") (pintype "power_in"))
      (node (ref "U5") (pin "11") (pinfunction "PVIN_11") (pintype "power_in"))
      (node (ref "U8") (pin "A2") (pinfunction "PVIN_A2") (pintype "passive"))
    )
    (net (code "36") (name "Vbat_in") (class "Default")
      (node (ref "BT1") (pin "1") (pinfunction "1_1") (pintype "passive"))
      (node (ref "C33") (pin "1") (pintype "passive"))
      (node (ref "Q1") (pin "2") (pinfunction "Source_2") (pintype "passive"))
      (node (ref "R23") (pin "2") (pintype "passive"))
      (node (ref "U7") (pin "1") (pinfunction "VDD_1") (pintype "power_in"))
    )
    (net (code "37") (name "unconnected-(U6-V--Pad5)") (class "Default")
      (node (ref "U6") (pin "5") (pinfunction "V-_5") (pintype "power_in"))
    )
    (net (code "38") (name "unconnected-(U15-NC-Pad2)") (class "Default")
      (node (ref "U15") (pin "2") (pinfunction "NC_2") (pintype "passive"))
    )
    (net (code "39") (name "unconnected-(U15-NC-Pad5)") (class "Default")
      (node (ref "U15") (pin "5") (pinfunction "NC_5") (pintype "passive"))
    )
  )
)
